# pi3_hat.net
KiCad netlist of a schematic drawn in EAGLE
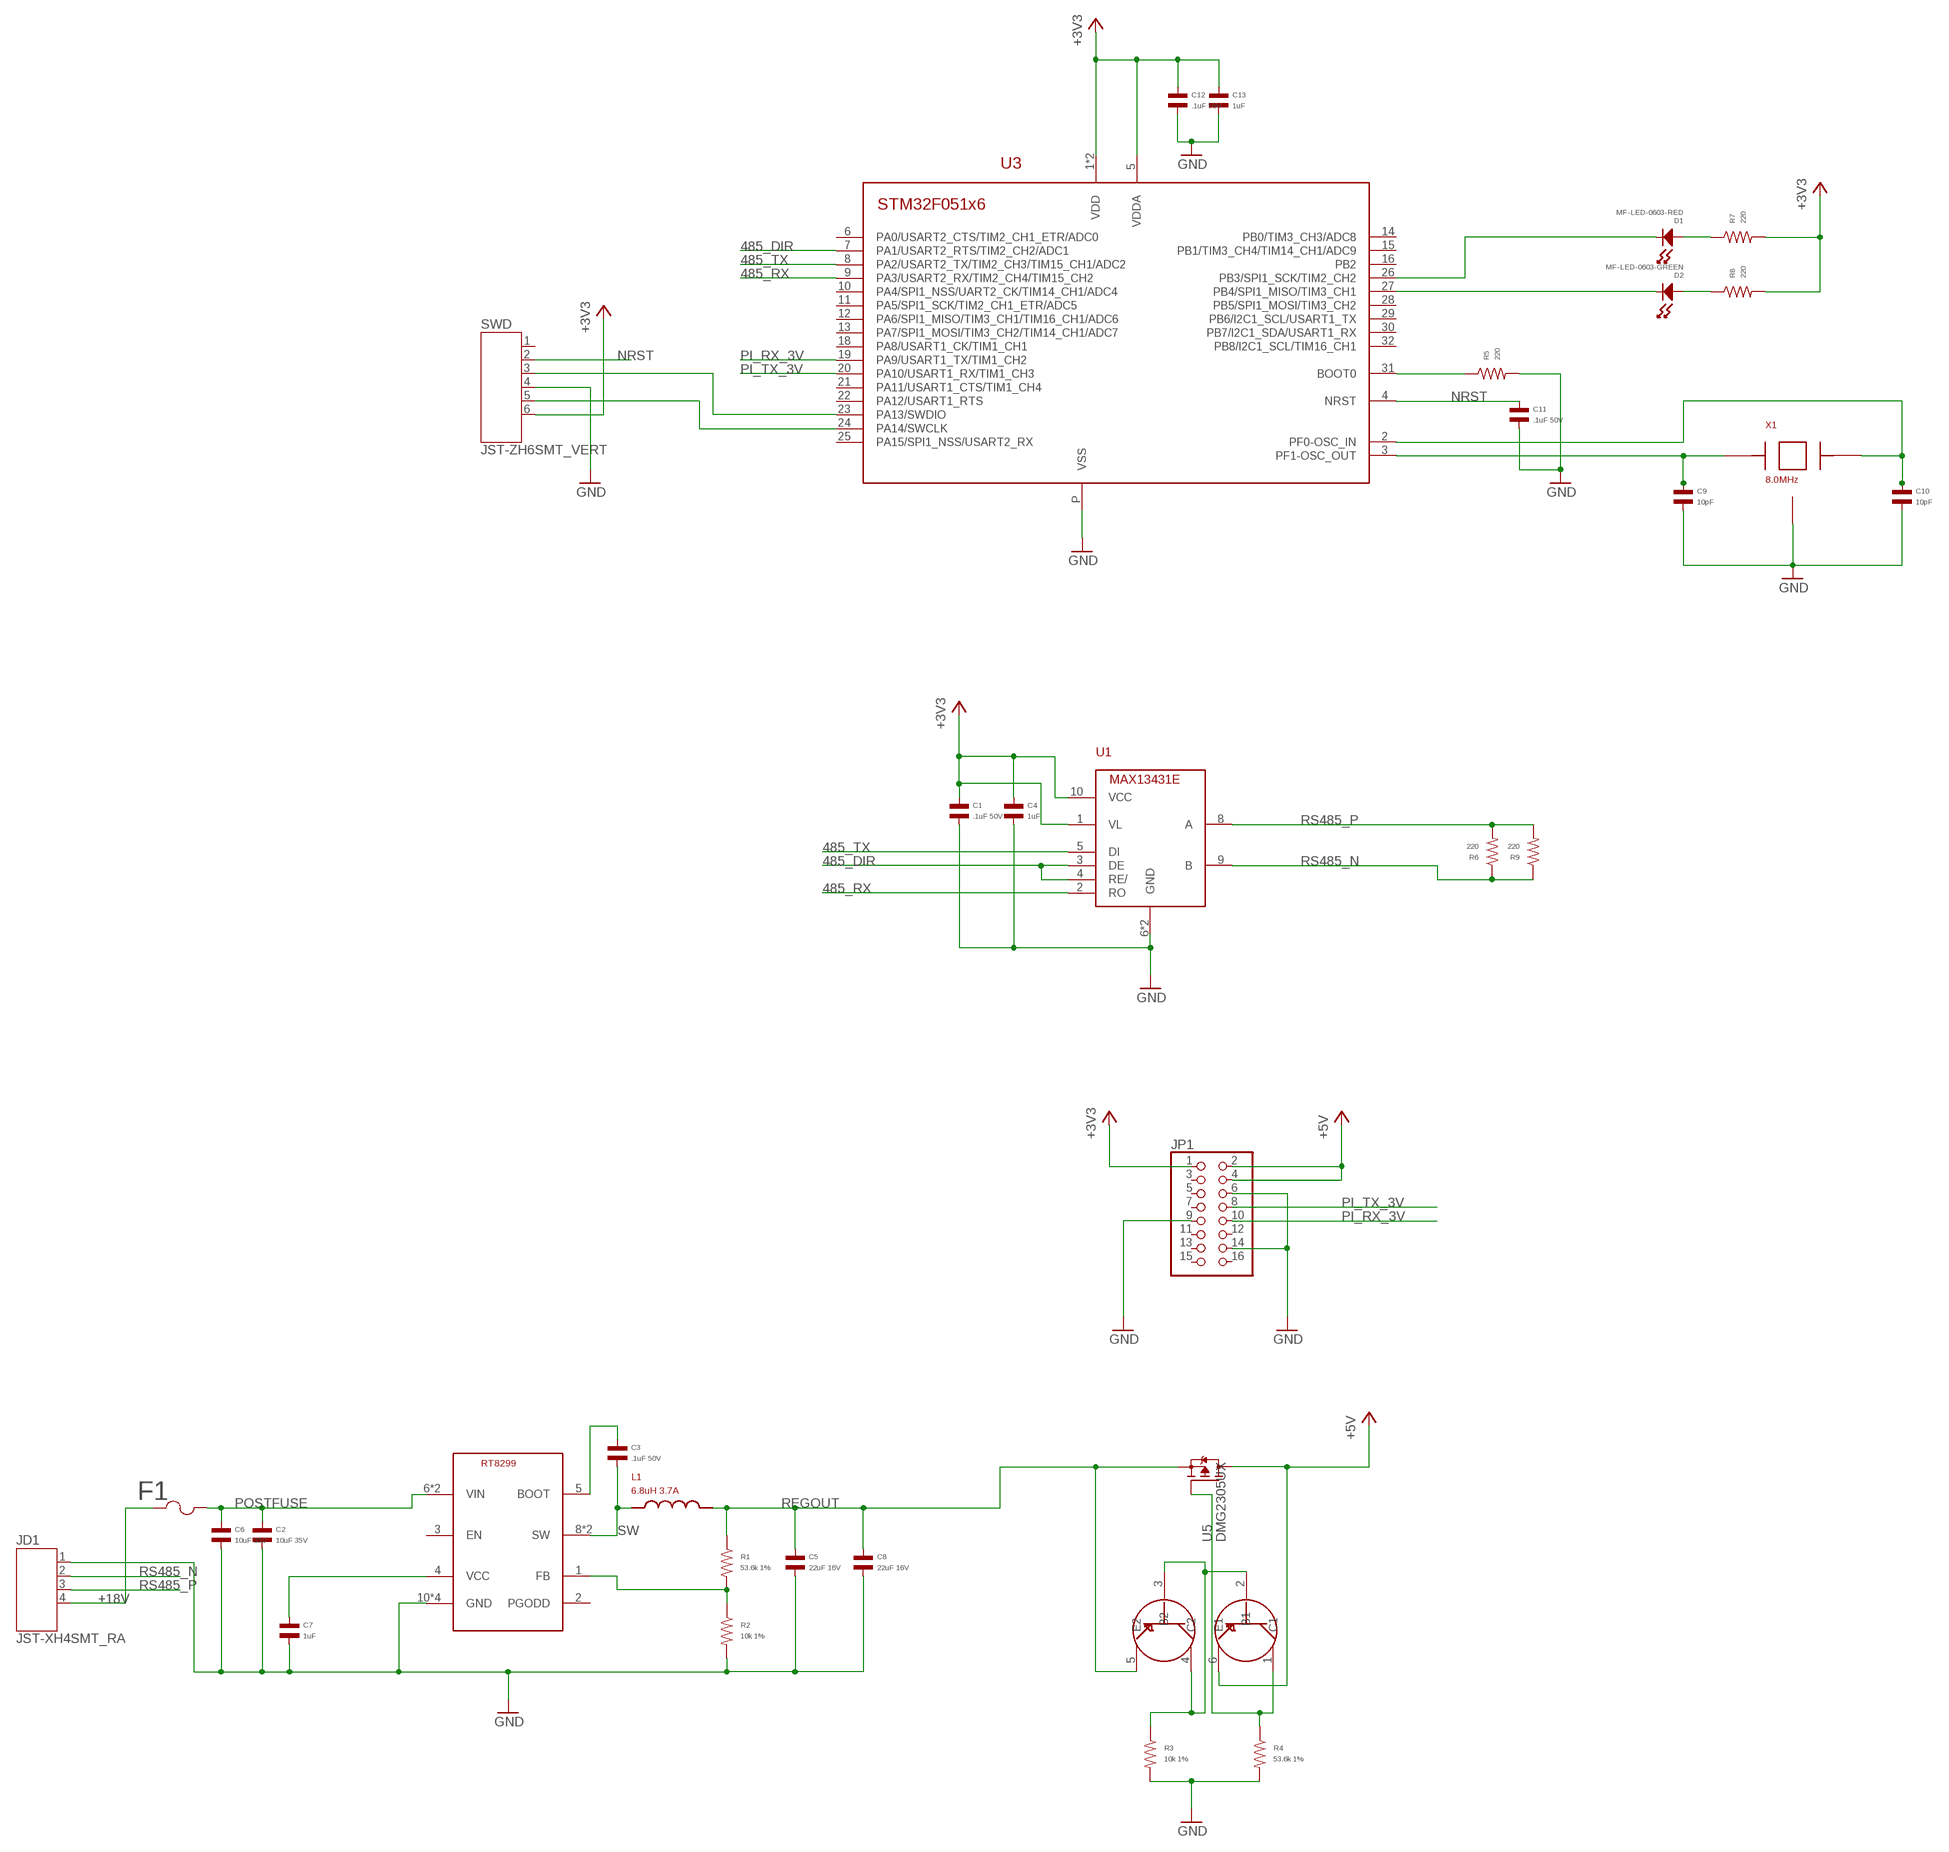
[diagram p0: schematic, sheet 1]

(export (version "E")
  (design (tool "Eeschema 10.0.6"))
  (components
    (comp (ref "C1")
      (value ".1uF 50V")
      (footprint "eagle-import:C0805")
      (fields (field (name "HOUSEPART") "1") (field (name "MPN") "MF-CAP-0805-0.1uF"))
      (libsource (lib "eagle-import") (part "CAPACITOR_NP_0805"))
    )
    (comp (ref "C2")
      (value "10uF 35V")
      (footprint "eagle-import:C1206")
      (fields (field (name "MF") "TDK") (field (name "MPN") "CGA5L1X7R1V106K160AC"))
      (libsource (lib "eagle-import") (part "CAPACITOR_NP_1206"))
    )
    (comp (ref "C3")
      (value ".1uF 50V")
      (footprint "eagle-import:C0805")
      (fields (field (name "HOUSEPART") "1") (field (name "MPN") "MF-CAP-0805-0.1uF"))
      (libsource (lib "eagle-import") (part "CAPACITOR_NP_0805"))
    )
    (comp (ref "C4")
      (value "1uF")
      (footprint "eagle-import:C0603")
      (fields (field (name "HOUSEPART") "1") (field (name "MPN") "MF-CAP-0603-1uF"))
      (libsource (lib "eagle-import") (part "CAPACITOR_NP_0603"))
    )
    (comp (ref "C5")
      (value "22uF 16V")
      (footprint "eagle-import:C1210")
      (fields (field (name "MF") "SAMSUNG") (field (name "MPN") "CL32A226KOJNNNE"))
      (libsource (lib "eagle-import") (part "CAPACITOR_NP_1210"))
    )
    (comp (ref "C6")
      (value "10uF 35V")
      (footprint "eagle-import:C1206")
      (fields (field (name "MF") "TDK") (field (name "MPN") "CGA5L1X7R1V106K160AC"))
      (libsource (lib "eagle-import") (part "CAPACITOR_NP_1206"))
    )
    (comp (ref "C7")
      (value "1uF")
      (footprint "eagle-import:C0603")
      (fields (field (name "HOUSEPART") "1") (field (name "MPN") "MF-CAP-0603-1uF"))
      (libsource (lib "eagle-import") (part "CAPACITOR_NP_0603"))
    )
    (comp (ref "C8")
      (value "22uF 16V")
      (footprint "eagle-import:C1210")
      (fields (field (name "MF") "SAMSUNG") (field (name "MPN") "CL32A226KOJNNNE"))
      (libsource (lib "eagle-import") (part "CAPACITOR_NP_1210"))
    )
    (comp (ref "C9")
      (value "10pF")
      (footprint "eagle-import:C0603")
      (fields
        (field (name "HOUSEPART") "1")
        (field (name "MF") "MACROFAB")
        (field (name "MPN") "MF-CAP-0603-10pF")
      )
      (libsource (lib "eagle-import") (part "CAPACITOR_NP_0603"))
    )
    (comp (ref "C10")
      (value "10pF")
      (footprint "eagle-import:C0603")
      (fields
        (field (name "HOUSEPART") "1")
        (field (name "MF") "MACROFAB")
        (field (name "MPN") "MF-CAP-0603-10pF")
      )
      (libsource (lib "eagle-import") (part "CAPACITOR_NP_0603"))
    )
    (comp (ref "C11")
      (value ".1uF 50V")
      (footprint "eagle-import:C0805")
      (fields (field (name "HOUSEPART") "1") (field (name "MPN") "MF-CAP-0805-0.1uF"))
      (libsource (lib "eagle-import") (part "CAPACITOR_NP_0805"))
    )
    (comp (ref "C12")
      (value ".1uF 50V")
      (footprint "eagle-import:C0805")
      (fields (field (name "HOUSEPART") "1") (field (name "MPN") "MF-CAP-0805-0.1uF"))
      (libsource (lib "eagle-import") (part "CAPACITOR_NP_0805"))
    )
    (comp (ref "C13")
      (value "1uF")
      (footprint "eagle-import:C0603")
      (fields (field (name "HOUSEPART") "1") (field (name "MPN") "MF-CAP-0603-1uF"))
      (libsource (lib "eagle-import") (part "CAPACITOR_NP_0603"))
    )
    (comp (ref "D1")
      (value "MF-LED-0603-RED")
      (footprint "eagle-import:LED0603")
      (fields (field (name "HOUSEPART") "YES"))
      (libsource (lib "eagle-import") (part "LED_SINGLE-0603-RED"))
    )
    (comp (ref "D2")
      (value "MF-LED-0603-GREEN")
      (footprint "eagle-import:LED0603")
      (fields (field (name "HOUSEPART") "YES"))
      (libsource (lib "eagle-import") (part "LED_SINGLE-0603-GREEN"))
    )
    (comp (ref "F1")
      (value "MFU0603FF04000P100")
      (footprint "eagle-import:FUS_VISHAY_MFU0603")
      (libsource (lib "eagle-import") (part "MFU0603FF04000P100"))
    )
    (comp (ref "JD1")
      (value "JST-XH4SMT_RA")
      (footprint "eagle-import:JST_XH_SMT_RA_4")
      (fields (field (name "MF") "JST") (field (name "MPN") "S4B-XH-SM4-TB(LF)(SN)"))
      (libsource (lib "eagle-import") (part "JST-XH4SMT_RA"))
    )
    (comp (ref "JP1")
      (value "PINHD-2X8")
      (footprint "eagle-import:2X08")
      (libsource (lib "eagle-import") (part "PINHD-2X8"))
    )
    (comp (ref "L1")
      (value "6.8uH 3.7A")
      (footprint "eagle-import:TAIYO_8040")
      (fields
        (field (name "HOUSEPART") "0")
        (field (name "MF") "TAIYO YUDEN")
        (field (name "MPN") "NR8040T6R8N")
      )
      (libsource (lib "eagle-import") (part "INDUCTORTAIYO_8040"))
    )
    (comp (ref "R1")
      (value "53.6k 1%")
      (footprint "eagle-import:R0603")
      (fields (field (name "MF") "Panasonic") (field (name "MPN") "ERJ-3EKF5362V"))
      (libsource (lib "eagle-import") (part "RESISTOR_0603"))
    )
    (comp (ref "R2")
      (value "10k 1%")
      (footprint "eagle-import:R0603")
      (fields (field (name "MF") "Panasonic") (field (name "MPN") "ERJ-3EKF1002V"))
      (libsource (lib "eagle-import") (part "RESISTOR_0603"))
    )
    (comp (ref "R3")
      (value "10k 1%")
      (footprint "eagle-import:R0603")
      (fields (field (name "MF") "Panasonic") (field (name "MPN") "ERJ-3EKF1002V"))
      (libsource (lib "eagle-import") (part "RESISTOR_0603"))
    )
    (comp (ref "R4")
      (value "53.6k 1%")
      (footprint "eagle-import:R0603")
      (fields (field (name "MF") "Panasonic") (field (name "MPN") "ERJ-3EKF5362V"))
      (libsource (lib "eagle-import") (part "RESISTOR_0603"))
    )
    (comp (ref "R5")
      (value "220")
      (footprint "eagle-import:R0603")
      (fields (field (name "MPN") "MF-RES-0603-220"))
      (libsource (lib "eagle-import") (part "RESISTOR_0603"))
    )
    (comp (ref "R6")
      (value "220")
      (footprint "eagle-import:R0603")
      (fields (field (name "MPN") "MF-RES-0603-220"))
      (libsource (lib "eagle-import") (part "RESISTOR_0603"))
    )
    (comp (ref "R7")
      (value "220")
      (footprint "eagle-import:R0603")
      (fields (field (name "MPN") "MF-RES-0603-220"))
      (libsource (lib "eagle-import") (part "RESISTOR_0603"))
    )
    (comp (ref "R8")
      (value "220")
      (footprint "eagle-import:R0603")
      (fields (field (name "MPN") "MF-RES-0603-220"))
      (libsource (lib "eagle-import") (part "RESISTOR_0603"))
    )
    (comp (ref "R9")
      (value "220")
      (footprint "eagle-import:R0603")
      (fields (field (name "MPN") "MF-RES-0603-220"))
      (libsource (lib "eagle-import") (part "RESISTOR_0603"))
    )
    (comp (ref "SWD")
      (value "JST-ZH6SMT_VERT")
      (footprint "eagle-import:JST_B6B-ZR-SM4-TF(LF)(SN)")
      (fields (field (name "MF") "JST") (field (name "MPN") "B6B-ZR-SM4-TF(LF)(SN)"))
      (libsource (lib "eagle-import") (part "JST-ZH6SMT_VERT"))
    )
    (comp (ref "U1")
      (value "MAX13431E")
      (footprint "eagle-import:TDFN10")
      (fields (field (name "MF") "Maxim") (field (name "MPN") "MAX13431EETB+T"))
      (libsource (lib "eagle-import") (part "MAX13431E"))
    )
    (comp (ref "U2")
      (value "RT829910L_DFN")
      (footprint "eagle-import:10L_DFN")
      (fields (field (name "MF") "Richtek") (field (name "MPN") "RT8299ZQW"))
      (libsource (lib "eagle-import") (part "RT829910L_DFN"))
    )
    (comp (ref "U3")
      (value "STM32F051X6UFQFPN32")
      (footprint "eagle-import:UFQFPN32")
      (fields (field (name "MF") "STMicroelectronics") (field (name "MPN") "STM32F051K6U6"))
      (libsource (lib "eagle-import") (part "STM32F051X6UFQFPN32"))
    )
    (comp (ref "U4")
      (value "DMMT5401")
      (footprint "eagle-import:SOT26")
      (fields (field (name "MF") "Didoes Incorporated") (field (name "MPN") "DMMT5401-7-F"))
      (libsource (lib "eagle-import") (part "DMMT5401"))
    )
    (comp (ref "U5")
      (value "DMG2305UX")
      (footprint "eagle-import:SOT23")
      (fields (field (name "MF") "Diodes Incorporated") (field (name "MPN") "DMG2305UX-13"))
      (libsource (lib "eagle-import") (part "DMG2305UX"))
    )
    (comp (ref "X1")
      (value "8.0MHz")
      (footprint "eagle-import:ABM3B")
      (fields (field (name "MF") "Abracon") (field (name "MPN") "ABM3B-8.000MHZ-10-1-U-T"))
      (libsource (lib "eagle-import") (part "CRYSTALABM3B"))
    )
  )
  (nets
    (net (code "1") (name "+3V3") (class "Default")
      (node (ref "C1") (pin "P$1") (pinfunction "P$1_P$1") (pintype "passive"))
      (node (ref "C12") (pin "P$1") (pinfunction "P$1_P$1") (pintype "passive"))
      (node (ref "C13") (pin "P$1") (pinfunction "P$1_P$1") (pintype "passive"))
      (node (ref "C4") (pin "P$1") (pinfunction "P$1_P$1") (pintype "passive"))
      (node (ref "JP1") (pin "1") (pinfunction "1_1") (pintype "passive"))
      (node (ref "R7") (pin "P$2") (pinfunction "P$2_P$2") (pintype "passive"))
      (node (ref "R8") (pin "P$2") (pinfunction "P$2_P$2") (pintype "passive"))
      (node (ref "SWD") (pin "6") (pinfunction "6_6") (pintype "passive"))
      (node (ref "U1") (pin "1") (pinfunction "VL_1") (pintype "bidirectional"))
      (node (ref "U1") (pin "10") (pinfunction "VCC_10") (pintype "bidirectional"))
      (node (ref "U3") (pin "1") (pinfunction "VDD_1") (pintype "bidirectional"))
      (node (ref "U3") (pin "17") (pinfunction "VDD_17") (pintype "bidirectional"))
      (node (ref "U3") (pin "5") (pinfunction "VDDA_5") (pintype "bidirectional"))
    )
    (net (code "2") (name "+5V") (class "Default")
      (node (ref "JP1") (pin "2") (pinfunction "2_2") (pintype "passive"))
      (node (ref "JP1") (pin "4") (pinfunction "4_4") (pintype "passive"))
      (node (ref "U4") (pin "6") (pinfunction "E1_6") (pintype "bidirectional"))
      (node (ref "U5") (pin "3") (pinfunction "D_3") (pintype "passive"))
    )
    (net (code "3") (name "/+18V") (class "Default")
      (node (ref "F1") (pin "1") (pinfunction "1_1") (pintype "passive"))
      (node (ref "JD1") (pin "4") (pinfunction "4_4") (pintype "passive"))
    )
    (net (code "4") (name "/485_DIR") (class "Default")
      (node (ref "U1") (pin "3") (pinfunction "DE_3") (pintype "bidirectional"))
      (node (ref "U1") (pin "4") (pinfunction "RE/_4") (pintype "bidirectional"))
      (node (ref "U3") (pin "7") (pinfunction "PA1/USART2_RTS/TIM2_CH2/ADC1_7") (pintype "bidirectional"))
    )
    (net (code "5") (name "/485_RX") (class "Default")
      (node (ref "U1") (pin "2") (pinfunction "RO_2") (pintype "bidirectional"))
      (node (ref "U3") (pin "9") (pinfunction "PA3/USART2_RX/TIM2_CH4/TIM15_CH2_9") (pintype "bidirectional"))
    )
    (net (code "6") (name "/485_TX") (class "Default")
      (node (ref "U1") (pin "5") (pinfunction "DI_5") (pintype "bidirectional"))
      (node (ref "U3") (pin "8") (pinfunction "PA2/USART2_TX/TIM2_CH3/TIM15_CH1/ADC2_8") (pintype "bidirectional"))
    )
    (net (code "7") (name "/NRST") (class "Default")
      (node (ref "C11") (pin "P$1") (pinfunction "P$1_P$1") (pintype "passive"))
      (node (ref "SWD") (pin "2") (pinfunction "2_2") (pintype "passive"))
      (node (ref "U3") (pin "4") (pinfunction "NRST_4") (pintype "bidirectional"))
    )
    (net (code "8") (name "/PI_RX_3V") (class "Default")
      (node (ref "JP1") (pin "10") (pinfunction "10_10") (pintype "passive"))
      (node (ref "U3") (pin "19") (pinfunction "PA9/USART1_TX/TIM1_CH2_19") (pintype "bidirectional"))
    )
    (net (code "9") (name "/PI_TX_3V") (class "Default")
      (node (ref "JP1") (pin "8") (pinfunction "8_8") (pintype "passive"))
      (node (ref "U3") (pin "20") (pinfunction "PA10/USART1_RX/TIM1_CH3_20") (pintype "bidirectional"))
    )
    (net (code "10") (name "/POSTFUSE") (class "Default")
      (node (ref "C2") (pin "P$1") (pinfunction "P$1_P$1") (pintype "passive"))
      (node (ref "C6") (pin "P$1") (pinfunction "P$1_P$1") (pintype "passive"))
      (node (ref "F1") (pin "2") (pinfunction "2_2") (pintype "passive"))
      (node (ref "U2") (pin "6") (pinfunction "VIN_6") (pintype "bidirectional"))
      (node (ref "U2") (pin "7") (pinfunction "VIN_7") (pintype "bidirectional"))
    )
    (net (code "11") (name "/REGOUT") (class "Default")
      (node (ref "C5") (pin "P$1") (pinfunction "P$1_P$1") (pintype "passive"))
      (node (ref "C8") (pin "P$1") (pinfunction "P$1_P$1") (pintype "passive"))
      (node (ref "L1") (pin "2") (pinfunction "P$2_2") (pintype "passive"))
      (node (ref "R1") (pin "P$1") (pinfunction "P$1_P$1") (pintype "passive"))
      (node (ref "U4") (pin "5") (pinfunction "E2_5") (pintype "bidirectional"))
      (node (ref "U5") (pin "2") (pinfunction "S_2") (pintype "passive"))
    )
    (net (code "12") (name "/RS485_N") (class "Default")
      (node (ref "JD1") (pin "2") (pinfunction "2_2") (pintype "passive"))
      (node (ref "R6") (pin "P$1") (pinfunction "P$1_P$1") (pintype "passive"))
      (node (ref "R9") (pin "P$1") (pinfunction "P$1_P$1") (pintype "passive"))
      (node (ref "U1") (pin "9") (pinfunction "B_9") (pintype "bidirectional"))
    )
    (net (code "13") (name "/RS485_P") (class "Default")
      (node (ref "JD1") (pin "3") (pinfunction "3_3") (pintype "passive"))
      (node (ref "R6") (pin "P$2") (pinfunction "P$2_P$2") (pintype "passive"))
      (node (ref "R9") (pin "P$2") (pinfunction "P$2_P$2") (pintype "passive"))
      (node (ref "U1") (pin "8") (pinfunction "A_8") (pintype "bidirectional"))
    )
    (net (code "14") (name "/SW") (class "Default")
      (node (ref "C3") (pin "P$2") (pinfunction "P$2_P$2") (pintype "passive"))
      (node (ref "L1") (pin "1") (pinfunction "P$1_1") (pintype "passive"))
      (node (ref "U2") (pin "8") (pinfunction "SW_8") (pintype "bidirectional"))
      (node (ref "U2") (pin "9") (pinfunction "SW_9") (pintype "bidirectional"))
    )
    (net (code "15") (name "GND") (class "Default")
      (node (ref "C1") (pin "P$2") (pinfunction "P$2_P$2") (pintype "passive"))
      (node (ref "C10") (pin "P$2") (pinfunction "P$2_P$2") (pintype "passive"))
      (node (ref "C11") (pin "P$2") (pinfunction "P$2_P$2") (pintype "passive"))
      (node (ref "C12") (pin "P$2") (pinfunction "P$2_P$2") (pintype "passive"))
      (node (ref "C13") (pin "P$2") (pinfunction "P$2_P$2") (pintype "passive"))
      (node (ref "C2") (pin "P$2") (pinfunction "P$2_P$2") (pintype "passive"))
      (node (ref "C4") (pin "P$2") (pinfunction "P$2_P$2") (pintype "passive"))
      (node (ref "C5") (pin "P$2") (pinfunction "P$2_P$2") (pintype "passive"))
      (node (ref "C6") (pin "P$2") (pinfunction "P$2_P$2") (pintype "passive"))
      (node (ref "C7") (pin "P$2") (pinfunction "P$2_P$2") (pintype "passive"))
      (node (ref "C8") (pin "P$2") (pinfunction "P$2_P$2") (pintype "passive"))
      (node (ref "C9") (pin "P$2") (pinfunction "P$2_P$2") (pintype "passive"))
      (node (ref "JD1") (pin "1") (pinfunction "1_1") (pintype "passive"))
      (node (ref "JP1") (pin "14") (pinfunction "14_14") (pintype "passive"))
      (node (ref "JP1") (pin "6") (pinfunction "6_6") (pintype "passive"))
      (node (ref "JP1") (pin "9") (pinfunction "9_9") (pintype "passive"))
      (node (ref "R2") (pin "P$2") (pinfunction "P$2_P$2") (pintype "passive"))
      (node (ref "R3") (pin "P$2") (pinfunction "P$2_P$2") (pintype "passive"))
      (node (ref "R4") (pin "P$2") (pinfunction "P$2_P$2") (pintype "passive"))
      (node (ref "R5") (pin "P$2") (pinfunction "P$2_P$2") (pintype "passive"))
      (node (ref "SWD") (pin "4") (pinfunction "4_4") (pintype "passive"))
      (node (ref "U1") (pin "6") (pinfunction "GND_6") (pintype "bidirectional"))
      (node (ref "U1") (pin "PAD") (pinfunction "GND_PAD") (pintype "bidirectional"))
      (node (ref "U2") (pin "10") (pinfunction "GND_10") (pintype "bidirectional"))
      (node (ref "U2") (pin "P0") (pinfunction "GND_P0") (pintype "bidirectional"))
      (node (ref "U2") (pin "P1") (pinfunction "GND_P1") (pintype "bidirectional"))
      (node (ref "U2") (pin "P2") (pinfunction "GND_P2") (pintype "bidirectional"))
      (node (ref "U3") (pin "P") (pinfunction "VSS_P") (pintype "bidirectional"))
      (node (ref "X1") (pin "2") (pinfunction "P$3_2") (pintype "bidirectional"))
      (node (ref "X1") (pin "4") (pinfunction "P$3_4") (pintype "bidirectional"))
    )
    (net (code "16") (name "Net-(D1-PadANODE)") (class "Default")
      (node (ref "D1") (pin "ANODE") (pinfunction "ANODE_ANODE") (pintype "power_in"))
      (node (ref "R7") (pin "P$1") (pinfunction "P$1_P$1") (pintype "passive"))
    )
    (net (code "17") (name "Net-(D2-PadANODE)") (class "Default")
      (node (ref "D2") (pin "ANODE") (pinfunction "ANODE_ANODE") (pintype "power_in"))
      (node (ref "R8") (pin "P$1") (pinfunction "P$1_P$1") (pintype "passive"))
    )
    (net (code "18") (name "Net-(U2-BOOT)") (class "Default")
      (node (ref "C3") (pin "P$1") (pinfunction "P$1_P$1") (pintype "passive"))
      (node (ref "U2") (pin "5") (pinfunction "BOOT_5") (pintype "bidirectional"))
    )
    (net (code "19") (name "Net-(U2-FB)") (class "Default")
      (node (ref "R1") (pin "P$2") (pinfunction "P$2_P$2") (pintype "passive"))
      (node (ref "R2") (pin "P$1") (pinfunction "P$1_P$1") (pintype "passive"))
      (node (ref "U2") (pin "1") (pinfunction "FB_1") (pintype "bidirectional"))
    )
    (net (code "20") (name "Net-(U2-VCC)") (class "Default")
      (node (ref "C7") (pin "P$1") (pinfunction "P$1_P$1") (pintype "passive"))
      (node (ref "U2") (pin "4") (pinfunction "VCC_4") (pintype "bidirectional"))
    )
    (net (code "21") (name "Net-(U3-BOOT0)") (class "Default")
      (node (ref "R5") (pin "P$1") (pinfunction "P$1_P$1") (pintype "passive"))
      (node (ref "U3") (pin "31") (pinfunction "BOOT0_31") (pintype "bidirectional"))
    )
    (net (code "22") (name "Net-(U3-PA13{slash}SWDIO)") (class "Default")
      (node (ref "SWD") (pin "3") (pinfunction "3_3") (pintype "passive"))
      (node (ref "U3") (pin "23") (pinfunction "PA13/SWDIO_23") (pintype "bidirectional"))
    )
    (net (code "23") (name "Net-(U3-PA14{slash}SWCLK)") (class "Default")
      (node (ref "SWD") (pin "5") (pinfunction "5_5") (pintype "passive"))
      (node (ref "U3") (pin "24") (pinfunction "PA14/SWCLK_24") (pintype "bidirectional"))
    )
    (net (code "24") (name "Net-(U3-PB3{slash}SPI1_SCK{slash}TIM2_CH2)") (class "Default")
      (node (ref "D1") (pin "CATHODE") (pinfunction "CATHODE_CATHODE") (pintype "power_in"))
      (node (ref "U3") (pin "26") (pinfunction "PB3/SPI1_SCK/TIM2_CH2_26") (pintype "bidirectional"))
    )
    (net (code "25") (name "Net-(U3-PB4{slash}SPI1_MISO{slash}TIM3_CH1)") (class "Default")
      (node (ref "D2") (pin "CATHODE") (pinfunction "CATHODE_CATHODE") (pintype "power_in"))
      (node (ref "U3") (pin "27") (pinfunction "PB4/SPI1_MISO/TIM3_CH1_27") (pintype "bidirectional"))
    )
    (net (code "26") (name "Net-(U3-PF0-OSC_IN)") (class "Default")
      (node (ref "C10") (pin "P$1") (pinfunction "P$1_P$1") (pintype "passive"))
      (node (ref "U3") (pin "2") (pinfunction "PF0-OSC_IN_2") (pintype "bidirectional"))
      (node (ref "X1") (pin "3") (pinfunction "P$2_3") (pintype "bidirectional"))
    )
    (net (code "27") (name "Net-(U3-PF1-OSC_OUT)") (class "Default")
      (node (ref "C9") (pin "P$1") (pinfunction "P$1_P$1") (pintype "passive"))
      (node (ref "U3") (pin "3") (pinfunction "PF1-OSC_OUT_3") (pintype "bidirectional"))
      (node (ref "X1") (pin "1") (pinfunction "P$1_1") (pintype "bidirectional"))
    )
    (net (code "28") (name "Net-(U4-B1)") (class "Default")
      (node (ref "R3") (pin "P$1") (pinfunction "P$1_P$1") (pintype "passive"))
      (node (ref "U4") (pin "2") (pinfunction "B1_2") (pintype "bidirectional"))
      (node (ref "U4") (pin "3") (pinfunction "B2_3") (pintype "bidirectional"))
      (node (ref "U4") (pin "4") (pinfunction "C2_4") (pintype "bidirectional"))
    )
    (net (code "29") (name "Net-(U4-C1)") (class "Default")
      (node (ref "R4") (pin "P$1") (pinfunction "P$1_P$1") (pintype "passive"))
      (node (ref "U4") (pin "1") (pinfunction "C1_1") (pintype "bidirectional"))
      (node (ref "U5") (pin "1") (pinfunction "G_1") (pintype "passive"))
    )
    (net (code "30") (name "unconnected-(JP1-Pad3)") (class "Default")
      (node (ref "JP1") (pin "3") (pinfunction "3_3") (pintype "passive"))
    )
    (net (code "31") (name "unconnected-(JP1-Pad5)") (class "Default")
      (node (ref "JP1") (pin "5") (pinfunction "5_5") (pintype "passive"))
    )
    (net (code "32") (name "unconnected-(JP1-Pad7)") (class "Default")
      (node (ref "JP1") (pin "7") (pinfunction "7_7") (pintype "passive"))
    )
    (net (code "33") (name "unconnected-(JP1-Pad11)") (class "Default")
      (node (ref "JP1") (pin "11") (pinfunction "11_11") (pintype "passive"))
    )
    (net (code "34") (name "unconnected-(JP1-Pad12)") (class "Default")
      (node (ref "JP1") (pin "12") (pinfunction "12_12") (pintype "passive"))
    )
    (net (code "35") (name "unconnected-(JP1-Pad13)") (class "Default")
      (node (ref "JP1") (pin "13") (pinfunction "13_13") (pintype "passive"))
    )
    (net (code "36") (name "unconnected-(JP1-Pad15)") (class "Default")
      (node (ref "JP1") (pin "15") (pinfunction "15_15") (pintype "passive"))
    )
    (net (code "37") (name "unconnected-(JP1-Pad16)") (class "Default")
      (node (ref "JP1") (pin "16") (pinfunction "16_16") (pintype "passive"))
    )
    (net (code "38") (name "unconnected-(SWD-Pad1)") (class "Default")
      (node (ref "SWD") (pin "1") (pinfunction "1_1") (pintype "passive"))
    )
    (net (code "39") (name "unconnected-(U2-EN-Pad3)") (class "Default")
      (node (ref "U2") (pin "3") (pinfunction "EN_3") (pintype "bidirectional"))
    )
    (net (code "40") (name "unconnected-(U2-PGODD-Pad2)") (class "Default")
      (node (ref "U2") (pin "2") (pinfunction "PGODD_2") (pintype "bidirectional"))
    )
    (net (code "41") (name "unconnected-(U3-PA0{slash}USART2_CTS{slash}TIM2_CH1_ETR{slash}ADC0-Pad6)") (class "Default")
      (node (ref "U3") (pin "6") (pinfunction "PA0/USART2_CTS/TIM2_CH1_ETR/ADC0_6") (pintype "bidirectional"))
    )
    (net (code "42") (name "unconnected-(U3-PA4{slash}SPI1_NSS{slash}UART2_CK{slash}TIM14_CH1{slash}ADC4-Pad10)") (class "Default")
      (node (ref "U3") (pin "10") (pinfunction "PA4/SPI1_NSS/UART2_CK/TIM14_CH1/ADC4_10") (pintype "bidirectional"))
    )
    (net (code "43") (name "unconnected-(U3-PA5{slash}SPI1_SCK{slash}TIM2_CH1_ETR{slash}ADC5-Pad11)") (class "Default")
      (node (ref "U3") (pin "11") (pinfunction "PA5/SPI1_SCK/TIM2_CH1_ETR/ADC5_11") (pintype "bidirectional"))
    )
    (net (code "44") (name "unconnected-(U3-PA6{slash}SPI1_MISO{slash}TIM3_CH1{slash}TIM16_CH1{slash}ADC6-Pad12)") (class "Default")
      (node (ref "U3") (pin "12") (pinfunction "PA6/SPI1_MISO/TIM3_CH1/TIM16_CH1/ADC6_12") (pintype "bidirectional"))
    )
    (net (code "45") (name "unconnected-(U3-PA7{slash}SPI1_MOSI{slash}TIM3_CH2{slash}TIM14_CH1{slash}ADC7-Pad13)") (class "Default")
      (node (ref "U3") (pin "13") (pinfunction "PA7/SPI1_MOSI/TIM3_CH2/TIM14_CH1/ADC7_13") (pintype "bidirectional"))
    )
    (net (code "46") (name "unconnected-(U3-PA8{slash}USART1_CK{slash}TIM1_CH1-Pad18)") (class "Default")
      (node (ref "U3") (pin "18") (pinfunction "PA8/USART1_CK/TIM1_CH1_18") (pintype "bidirectional"))
    )
    (net (code "47") (name "unconnected-(U3-PA11{slash}USART1_CTS{slash}TIM1_CH4-Pad21)") (class "Default")
      (node (ref "U3") (pin "21") (pinfunction "PA11/USART1_CTS/TIM1_CH4_21") (pintype "bidirectional"))
    )
    (net (code "48") (name "unconnected-(U3-PA12{slash}USART1_RTS-Pad22)") (class "Default")
      (node (ref "U3") (pin "22") (pinfunction "PA12/USART1_RTS_22") (pintype "bidirectional"))
    )
    (net (code "49") (name "unconnected-(U3-PA15{slash}SPI1_NSS{slash}USART2_RX-Pad25)") (class "Default")
      (node (ref "U3") (pin "25") (pinfunction "PA15/SPI1_NSS/USART2_RX_25") (pintype "bidirectional"))
    )
    (net (code "50") (name "unconnected-(U3-PB0{slash}TIM3_CH3{slash}ADC8-Pad14)") (class "Default")
      (node (ref "U3") (pin "14") (pinfunction "PB0/TIM3_CH3/ADC8_14") (pintype "bidirectional"))
    )
    (net (code "51") (name "unconnected-(U3-PB1{slash}TIM3_CH4{slash}TIM14_CH1{slash}ADC9-Pad15)") (class "Default")
      (node (ref "U3") (pin "15") (pinfunction "PB1/TIM3_CH4/TIM14_CH1/ADC9_15") (pintype "bidirectional"))
    )
    (net (code "52") (name "unconnected-(U3-PB2-Pad16)") (class "Default")
      (node (ref "U3") (pin "16") (pinfunction "PB2_16") (pintype "bidirectional"))
    )
    (net (code "53") (name "unconnected-(U3-PB5{slash}SPI1_MOSI{slash}TIM3_CH2-Pad28)") (class "Default")
      (node (ref "U3") (pin "28") (pinfunction "PB5/SPI1_MOSI/TIM3_CH2_28") (pintype "bidirectional"))
    )
    (net (code "54") (name "unconnected-(U3-PB6{slash}I2C1_SCL{slash}USART1_TX-Pad29)") (class "Default")
      (node (ref "U3") (pin "29") (pinfunction "PB6/I2C1_SCL/USART1_TX_29") (pintype "bidirectional"))
    )
    (net (code "55") (name "unconnected-(U3-PB7{slash}I2C1_SDA{slash}USART1_RX-Pad30)") (class "Default")
      (node (ref "U3") (pin "30") (pinfunction "PB7/I2C1_SDA/USART1_RX_30") (pintype "bidirectional"))
    )
    (net (code "56") (name "unconnected-(U3-PB8{slash}I2C1_SCL{slash}TIM16_CH1-Pad32)") (class "Default")
      (node (ref "U3") (pin "32") (pinfunction "PB8/I2C1_SCL/TIM16_CH1_32") (pintype "bidirectional"))
    )
  )
)
